# STM32Fx.net
KiCad netlist of a schematic drawn in Altium Designer
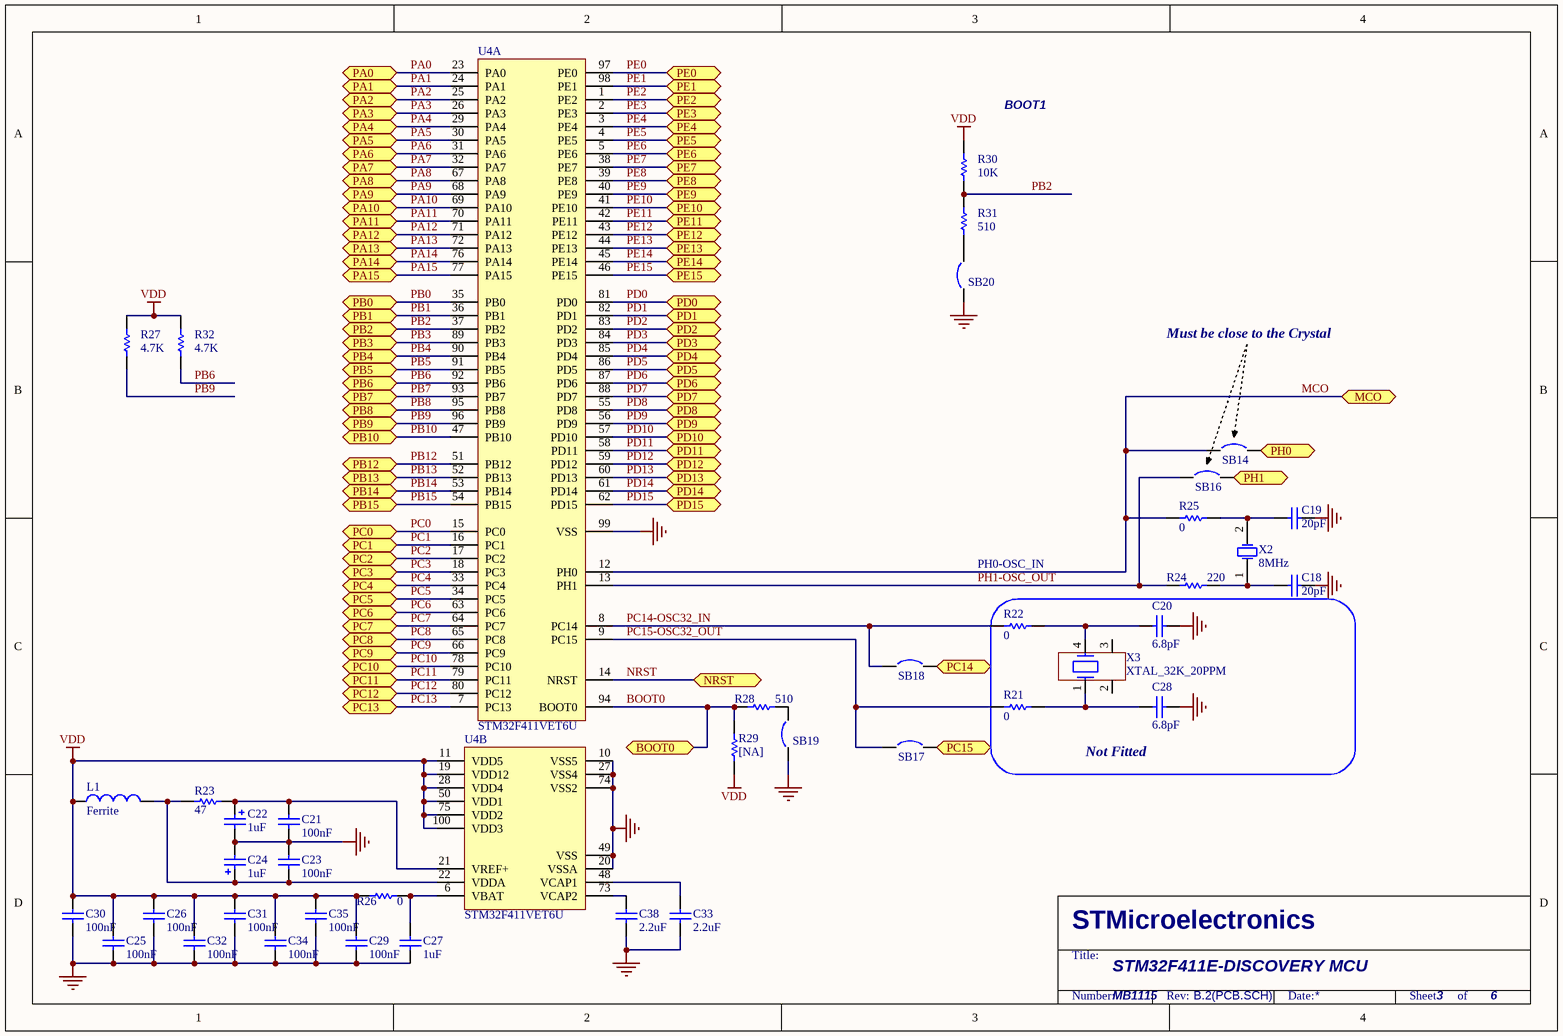
[diagram p0: STM32Fx.SchDoc]

(export (version "E")
  (design (tool "Eeschema 10.0.6"))
  (components
    (comp (ref "C18")
      (value "20pF")
      (footprint "0402C")
      (description "Capacitor,20pF,50V,NPO,5%,0402,YAGEO")
      (libsource (lib "MCD_TOOLS") (part "Cap_20pF_NPO_5%_0402"))
    )
    (comp (ref "C19")
      (value "20pF")
      (footprint "0402C")
      (description "Capacitor,20pF,50V,NPO,5%,0402,YAGEO")
      (libsource (lib "MCD_TOOLS") (part "Cap_20pF_NPO_5%_0402"))
    )
    (comp (ref "C20")
      (value "6.8pF")
      (footprint "0402C")
      (description "Capacitor,6.8pF,50V,NPO,4%,0402,AVX")
      (libsource (lib "MCD_TOOLS") (part "Cap_6.8pF_NPO_4%_0402"))
    )
    (comp (ref "C21")
      (value "100nF")
      (footprint "0402C")
      (description "Capacitor,100nF,16V,X7R,10%,0402,YAGEO")
      (libsource (lib "MCD_TOOLS") (part "Cap_100nF_X7R_10%_0402"))
    )
    (comp (ref "C22")
      (value "1uF")
      (footprint "TAN-A")
      (description "Polarized Capacitor,1uF,16V,10%,typeA,AVX")
      (libsource (lib "MCD_TOOLS") (part "Cap_1uF_POL_10%_TANA"))
    )
    (comp (ref "C23")
      (value "100nF")
      (footprint "0402C")
      (description "Capacitor,100nF,16V,X7R,10%,0402,YAGEO")
      (libsource (lib "MCD_TOOLS") (part "Cap_100nF_X7R_10%_0402"))
    )
    (comp (ref "C24")
      (value "1uF")
      (footprint "TAN-A")
      (description "Polarized Capacitor,1uF,16V,10%,typeA,AVX")
      (libsource (lib "MCD_TOOLS") (part "Cap_1uF_POL_10%_TANA"))
    )
    (comp (ref "C25")
      (value "100nF")
      (footprint "0402C")
      (description "Capacitor,100nF,16V,X7R,10%,0402,YAGEO")
      (libsource (lib "MCD_TOOLS") (part "Cap_100nF_X7R_10%_0402"))
    )
    (comp (ref "C26")
      (value "100nF")
      (footprint "0402C")
      (description "Capacitor,100nF,16V,X7R,10%,0402,YAGEO")
      (libsource (lib "MCD_TOOLS") (part "Cap_100nF_X7R_10%_0402"))
    )
    (comp (ref "C27")
      (value "1uF")
      (footprint "0603C")
      (description "Capacitor,1uF,16V,X5R,10%,0603,YAGEO")
      (libsource (lib "MCD_TOOLS") (part "Cap_1uF_X5R_10%_0603"))
    )
    (comp (ref "C28")
      (value "6.8pF")
      (footprint "0402C")
      (description "Capacitor,6.8pF,50V,NPO,4%,0402,AVX")
      (libsource (lib "MCD_TOOLS") (part "Cap_6.8pF_NPO_4%_0402"))
    )
    (comp (ref "C29")
      (value "100nF")
      (footprint "0402C")
      (description "Capacitor,100nF,16V,X7R,10%,0402,YAGEO")
      (libsource (lib "MCD_TOOLS") (part "Cap_100nF_X7R_10%_0402"))
    )
    (comp (ref "C30")
      (value "100nF")
      (footprint "0402C")
      (description "Capacitor,100nF,16V,X7R,10%,0402,YAGEO")
      (libsource (lib "MCD_TOOLS") (part "Cap_100nF_X7R_10%_0402"))
    )
    (comp (ref "C31")
      (value "100nF")
      (footprint "0402C")
      (description "Capacitor,100nF,16V,X7R,10%,0402,YAGEO")
      (libsource (lib "MCD_TOOLS") (part "Cap_100nF_X7R_10%_0402"))
    )
    (comp (ref "C32")
      (value "100nF")
      (footprint "0402C")
      (description "Capacitor,100nF,16V,X7R,10%,0402,YAGEO")
      (libsource (lib "MCD_TOOLS") (part "Cap_100nF_X7R_10%_0402"))
    )
    (comp (ref "C33")
      (value "2.2uF")
      (footprint "TAN-A")
      (description "Capacitor,2.2uF,16V, X7R,10%,0805,YAGEO")
      (libsource (lib "MCD_TOOLS") (part "Cap_2.2uF_X7R_10%_0805"))
    )
    (comp (ref "C34")
      (value "100nF")
      (footprint "0402C")
      (description "Capacitor,100nF,16V,X7R,10%,0402,YAGEO")
      (libsource (lib "MCD_TOOLS") (part "Cap_100nF_X7R_10%_0402"))
    )
    (comp (ref "C35")
      (value "100nF")
      (footprint "0402C")
      (description "Capacitor,100nF,16V,X7R,10%,0402,YAGEO")
      (libsource (lib "MCD_TOOLS") (part "Cap_100nF_X7R_10%_0402"))
    )
    (comp (ref "C38")
      (value "2.2uF")
      (footprint "TAN-A")
      (description "Capacitor,2.2uF,16V, X7R,10%,0805,YAGEO")
      (libsource (lib "MCD_TOOLS") (part "Cap_2.2uF_X7R_10%_0805"))
    )
    (comp (ref "L1")
      (value "Ferrite")
      (footprint "0603L")
      (description "Bead,600R,350mA,0603,FCM1608KF-601T03,Tai-tech")
      (libsource (lib "MCD_TOOLS") (part "BEAD_600R_350MA_0603"))
    )
    (comp (ref "R21")
      (value "0")
      (footprint "STM-SMEE:0402R")
      (description "Resistor,0,0402")
      (libsource (lib "MCD_TOOLS") (part "Res_0_0402"))
    )
    (comp (ref "R22")
      (value "0")
      (footprint "STM-SMEE:0402R")
      (description "Resistor,0,0402")
      (libsource (lib "MCD_TOOLS") (part "Res_0_0402"))
    )
    (comp (ref "R23")
      (value "47")
      (footprint "0402R")
      (description "Resistor")
      (fields (field (name "PUBLISHER") "Altium Limited"))
      (libsource (lib "Miscellaneous Devices") (part "Res1"))
    )
    (comp (ref "R24")
      (value "220")
      (footprint "0402R")
      (description "Resistor")
      (fields (field (name "PUBLISHER") "Altium Limited"))
      (libsource (lib "Miscellaneous Devices") (part "Res1"))
    )
    (comp (ref "R25")
      (value "0")
      (footprint "STM-SMEE:0402R")
      (description "Resistor,0,0402")
      (libsource (lib "MCD_TOOLS") (part "Res_0_0402"))
    )
    (comp (ref "R26")
      (value "0")
      (footprint "STM-SMEE:0402R")
      (description "Resistor,0,0402")
      (libsource (lib "MCD_TOOLS") (part "Res_0_0402"))
    )
    (comp (ref "R27")
      (value "4.7K")
      (footprint "0402R")
      (description "Resistor")
      (fields (field (name "PUBLISHER") "Altium Limited"))
      (libsource (lib "Miscellaneous Devices") (part "res1"))
    )
    (comp (ref "R28")
      (value "510")
      (footprint "0402R")
      (description "Resistor")
      (fields (field (name "PUBLISHER") "Altium Limited"))
      (libsource (lib "Miscellaneous Devices") (part "Res1"))
    )
    (comp (ref "R29")
      (value "[NA]")
      (footprint "STM-SMEE:0402R")
      (description "Resistor,[NA],0402")
      (libsource (lib "MCD_TOOLS") (part "Res_NA_0402"))
    )
    (comp (ref "R30")
      (value "10K")
      (footprint "0402R")
      (description "Resistor")
      (fields (field (name "PUBLISHER") "Altium Limited"))
      (libsource (lib "Miscellaneous Devices") (part "res1"))
    )
    (comp (ref "R31")
      (value "510")
      (footprint "0402R")
      (description "Resistor")
      (fields (field (name "PUBLISHER") "Altium Limited"))
      (libsource (lib "Miscellaneous Devices") (part "res1"))
    )
    (comp (ref "R32")
      (value "4.7K")
      (footprint "0402R")
      (description "Resistor")
      (fields (field (name "PUBLISHER") "Altium Limited"))
      (libsource (lib "Miscellaneous Devices") (part "res1"))
    )
    (comp (ref "SB14")
      (value "Circuit Breaker")
      (footprint "JP2_SMD")
      (libsource (lib "MCD_TOOLS") (part "Circuit Breaker"))
    )
    (comp (ref "SB16")
      (value "Circuit Breaker")
      (footprint "JP2_SMD")
      (libsource (lib "MCD_TOOLS") (part "Circuit Breaker"))
    )
    (comp (ref "SB17")
      (value "Circuit Breaker")
      (footprint "JP2_SMD")
      (libsource (lib "MCD_TOOLS") (part "Circuit Breaker"))
    )
    (comp (ref "SB18")
      (value "Circuit Breaker")
      (footprint "JP2_SMD")
      (libsource (lib "MCD_TOOLS") (part "Circuit Breaker"))
    )
    (comp (ref "SB19")
      (value "Circuit Breaker")
      (footprint "JP2_SMD")
      (libsource (lib "MCD_TOOLS") (part "Circuit Breaker"))
    )
    (comp (ref "SB20")
      (value "Circuit Breaker")
      (footprint "JP2_SMD")
      (libsource (lib "MCD_TOOLS") (part "Circuit Breaker"))
    )
    (comp (ref "U4")
      (value "STM32F411VET6U")
      (footprint "TQFP100")
      (description "STM32 Tiny Manta (STM32F401VCT6U)")
      (libsource (lib "MCD_TOOLS") (part "STM32F401VCT6U"))
    )
    (comp (ref "X2")
      (value "8MHz")
      (footprint "STM-SMEE:XTAL1")
      (description "Crystal Oscillator,8Mhz,20PF,20PPM,-10-70 degree,DIP,HC-49S")
      (libsource (lib "MCD_TOOLS") (part "XTAL_8MHZ_20PPM"))
    )
    (comp (ref "X3")
      (value "XTAL_32K_20PPM")
      (footprint "STM-SMEE:MC306-CRYSTAL")
      (description "crystal oscillator for clock,32.768K,6PF,20PPM,-40~85 degree,SMT,ETMB32.768W060BMPF")
      (libsource (lib "MCD_TOOLS") (part "XTAL_32K"))
    )
  )
  (nets
    (net (code "1") (name "/BOOT0") (class "Default")
      (node (ref "R28") (pin "2") (pinfunction "2_2") (pintype "passive"))
      (node (ref "R29") (pin "2") (pinfunction "2_2") (pintype "passive"))
      (node (ref "U4") (pin "94") (pinfunction "BOOT0_94") (pintype "passive"))
    )
    (net (code "2") (name "/MCO") (class "Default")
      (node (ref "R25") (pin "1") (pinfunction "1_1") (pintype "passive"))
      (node (ref "SB14") (pin "1") (pinfunction "1_1") (pintype "passive"))
      (node (ref "U4") (pin "12") (pinfunction "PH0_12") (pintype "passive"))
    )
    (net (code "3") (name "/NRST") (class "Default")
      (node (ref "U4") (pin "14") (pinfunction "NRST_14") (pintype "passive"))
    )
    (net (code "4") (name "/PA0") (class "Default")
      (node (ref "U4") (pin "23") (pinfunction "PA0_23") (pintype "passive"))
    )
    (net (code "5") (name "/PA1") (class "Default")
      (node (ref "U4") (pin "24") (pinfunction "PA1_24") (pintype "passive"))
    )
    (net (code "6") (name "/PA2") (class "Default")
      (node (ref "U4") (pin "25") (pinfunction "PA2_25") (pintype "passive"))
    )
    (net (code "7") (name "/PA3") (class "Default")
      (node (ref "U4") (pin "26") (pinfunction "PA3_26") (pintype "passive"))
    )
    (net (code "8") (name "/PA4") (class "Default")
      (node (ref "U4") (pin "29") (pinfunction "PA4_29") (pintype "passive"))
    )
    (net (code "9") (name "/PA5") (class "Default")
      (node (ref "U4") (pin "30") (pinfunction "PA5_30") (pintype "passive"))
    )
    (net (code "10") (name "/PA6") (class "Default")
      (node (ref "U4") (pin "31") (pinfunction "PA6_31") (pintype "passive"))
    )
    (net (code "11") (name "/PA7") (class "Default")
      (node (ref "U4") (pin "32") (pinfunction "PA7_32") (pintype "passive"))
    )
    (net (code "12") (name "/PA8") (class "Default")
      (node (ref "U4") (pin "67") (pinfunction "PA8_67") (pintype "passive"))
    )
    (net (code "13") (name "/PA9") (class "Default")
      (node (ref "U4") (pin "68") (pinfunction "PA9_68") (pintype "passive"))
    )
    (net (code "14") (name "/PA10") (class "Default")
      (node (ref "U4") (pin "69") (pinfunction "PA10_69") (pintype "passive"))
    )
    (net (code "15") (name "/PA11") (class "Default")
      (node (ref "U4") (pin "70") (pinfunction "PA11_70") (pintype "passive"))
    )
    (net (code "16") (name "/PA12") (class "Default")
      (node (ref "U4") (pin "71") (pinfunction "PA12_71") (pintype "passive"))
    )
    (net (code "17") (name "/PA13") (class "Default")
      (node (ref "U4") (pin "72") (pinfunction "PA13_72") (pintype "passive"))
    )
    (net (code "18") (name "/PA14") (class "Default")
      (node (ref "U4") (pin "76") (pinfunction "PA14_76") (pintype "passive"))
    )
    (net (code "19") (name "/PA15") (class "Default")
      (node (ref "U4") (pin "77") (pinfunction "PA15_77") (pintype "passive"))
    )
    (net (code "20") (name "/PB0") (class "Default")
      (node (ref "U4") (pin "35") (pinfunction "PB0_35") (pintype "passive"))
    )
    (net (code "21") (name "/PB1") (class "Default")
      (node (ref "U4") (pin "36") (pinfunction "PB1_36") (pintype "passive"))
    )
    (net (code "22") (name "/PB2") (class "Default")
      (node (ref "R30") (pin "2") (pinfunction "2_2") (pintype "passive"))
      (node (ref "R31") (pin "1") (pinfunction "1_1") (pintype "passive"))
      (node (ref "U4") (pin "37") (pinfunction "PB2_37") (pintype "passive"))
    )
    (net (code "23") (name "/PB3") (class "Default")
      (node (ref "U4") (pin "89") (pinfunction "PB3_89") (pintype "passive"))
    )
    (net (code "24") (name "/PB4") (class "Default")
      (node (ref "U4") (pin "90") (pinfunction "PB4_90") (pintype "passive"))
    )
    (net (code "25") (name "/PB5") (class "Default")
      (node (ref "U4") (pin "91") (pinfunction "PB5_91") (pintype "passive"))
    )
    (net (code "26") (name "/PB6") (class "Default")
      (node (ref "R32") (pin "2") (pinfunction "2_2") (pintype "passive"))
      (node (ref "U4") (pin "92") (pinfunction "PB6_92") (pintype "passive"))
    )
    (net (code "27") (name "/PB7") (class "Default")
      (node (ref "U4") (pin "93") (pinfunction "PB7_93") (pintype "passive"))
    )
    (net (code "28") (name "/PB8") (class "Default")
      (node (ref "U4") (pin "95") (pinfunction "PB8_95") (pintype "passive"))
    )
    (net (code "29") (name "/PB9") (class "Default")
      (node (ref "R27") (pin "2") (pinfunction "2_2") (pintype "passive"))
      (node (ref "U4") (pin "96") (pinfunction "PB9_96") (pintype "passive"))
    )
    (net (code "30") (name "/PB10") (class "Default")
      (node (ref "U4") (pin "47") (pinfunction "PB10_47") (pintype "passive"))
    )
    (net (code "31") (name "/PB12") (class "Default")
      (node (ref "U4") (pin "51") (pinfunction "PB12_51") (pintype "passive"))
    )
    (net (code "32") (name "/PB13") (class "Default")
      (node (ref "U4") (pin "52") (pinfunction "PB13_52") (pintype "passive"))
    )
    (net (code "33") (name "/PB14") (class "Default")
      (node (ref "U4") (pin "53") (pinfunction "PB14_53") (pintype "passive"))
    )
    (net (code "34") (name "/PB15") (class "Default")
      (node (ref "U4") (pin "54") (pinfunction "PB15_54") (pintype "passive"))
    )
    (net (code "35") (name "/PC0") (class "Default")
      (node (ref "U4") (pin "15") (pinfunction "PC0_15") (pintype "passive"))
    )
    (net (code "36") (name "/PC1") (class "Default")
      (node (ref "U4") (pin "16") (pinfunction "PC1_16") (pintype "passive"))
    )
    (net (code "37") (name "/PC2") (class "Default")
      (node (ref "U4") (pin "17") (pinfunction "PC2_17") (pintype "passive"))
    )
    (net (code "38") (name "/PC3") (class "Default")
      (node (ref "U4") (pin "18") (pinfunction "PC3_18") (pintype "passive"))
    )
    (net (code "39") (name "/PC4") (class "Default")
      (node (ref "U4") (pin "33") (pinfunction "PC4_33") (pintype "passive"))
    )
    (net (code "40") (name "/PC5") (class "Default")
      (node (ref "U4") (pin "34") (pinfunction "PC5_34") (pintype "passive"))
    )
    (net (code "41") (name "/PC6") (class "Default")
      (node (ref "U4") (pin "63") (pinfunction "PC6_63") (pintype "passive"))
    )
    (net (code "42") (name "/PC7") (class "Default")
      (node (ref "U4") (pin "64") (pinfunction "PC7_64") (pintype "passive"))
    )
    (net (code "43") (name "/PC8") (class "Default")
      (node (ref "U4") (pin "65") (pinfunction "PC8_65") (pintype "passive"))
    )
    (net (code "44") (name "/PC9") (class "Default")
      (node (ref "U4") (pin "66") (pinfunction "PC9_66") (pintype "passive"))
    )
    (net (code "45") (name "/PC10") (class "Default")
      (node (ref "U4") (pin "78") (pinfunction "PC10_78") (pintype "passive"))
    )
    (net (code "46") (name "/PC11") (class "Default")
      (node (ref "U4") (pin "79") (pinfunction "PC11_79") (pintype "passive"))
    )
    (net (code "47") (name "/PC12") (class "Default")
      (node (ref "U4") (pin "80") (pinfunction "PC12_80") (pintype "passive"))
    )
    (net (code "48") (name "/PC13") (class "Default")
      (node (ref "U4") (pin "7") (pinfunction "PC13_7") (pintype "passive"))
    )
    (net (code "49") (name "/PC14") (class "Default")
      (node (ref "SB18") (pin "2") (pinfunction "2_2") (pintype "passive"))
    )
    (net (code "50") (name "/PC14-OSC32_IN") (class "Default")
      (node (ref "R22") (pin "1") (pinfunction "1_1") (pintype "passive"))
      (node (ref "SB18") (pin "1") (pinfunction "1_1") (pintype "passive"))
      (node (ref "U4") (pin "8") (pinfunction "PC14_8") (pintype "passive"))
    )
    (net (code "51") (name "/PC15") (class "Default")
      (node (ref "SB17") (pin "2") (pinfunction "2_2") (pintype "passive"))
    )
    (net (code "52") (name "/PC15-OSC32_OUT") (class "Default")
      (node (ref "R21") (pin "1") (pinfunction "1_1") (pintype "passive"))
      (node (ref "SB17") (pin "1") (pinfunction "1_1") (pintype "passive"))
      (node (ref "U4") (pin "9") (pinfunction "PC15_9") (pintype "passive"))
    )
    (net (code "53") (name "/PD0") (class "Default")
      (node (ref "U4") (pin "81") (pinfunction "PD0_81") (pintype "passive"))
    )
    (net (code "54") (name "/PD1") (class "Default")
      (node (ref "U4") (pin "82") (pinfunction "PD1_82") (pintype "passive"))
    )
    (net (code "55") (name "/PD2") (class "Default")
      (node (ref "U4") (pin "83") (pinfunction "PD2_83") (pintype "passive"))
    )
    (net (code "56") (name "/PD3") (class "Default")
      (node (ref "U4") (pin "84") (pinfunction "PD3_84") (pintype "passive"))
    )
    (net (code "57") (name "/PD4") (class "Default")
      (node (ref "U4") (pin "85") (pinfunction "PD4_85") (pintype "passive"))
    )
    (net (code "58") (name "/PD5") (class "Default")
      (node (ref "U4") (pin "86") (pinfunction "PD5_86") (pintype "passive"))
    )
    (net (code "59") (name "/PD6") (class "Default")
      (node (ref "U4") (pin "87") (pinfunction "PD6_87") (pintype "passive"))
    )
    (net (code "60") (name "/PD7") (class "Default")
      (node (ref "U4") (pin "88") (pinfunction "PD7_88") (pintype "passive"))
    )
    (net (code "61") (name "/PD8") (class "Default")
      (node (ref "U4") (pin "55") (pinfunction "PD8_55") (pintype "passive"))
    )
    (net (code "62") (name "/PD9") (class "Default")
      (node (ref "U4") (pin "56") (pinfunction "PD9_56") (pintype "passive"))
    )
    (net (code "63") (name "/PD10") (class "Default")
      (node (ref "U4") (pin "57") (pinfunction "PD10_57") (pintype "passive"))
    )
    (net (code "64") (name "/PD11") (class "Default")
      (node (ref "U4") (pin "58") (pinfunction "PD11_58") (pintype "passive"))
    )
    (net (code "65") (name "/PD12") (class "Default")
      (node (ref "U4") (pin "59") (pinfunction "PD12_59") (pintype "passive"))
    )
    (net (code "66") (name "/PD13") (class "Default")
      (node (ref "U4") (pin "60") (pinfunction "PD13_60") (pintype "passive"))
    )
    (net (code "67") (name "/PD14") (class "Default")
      (node (ref "U4") (pin "61") (pinfunction "PD14_61") (pintype "passive"))
    )
    (net (code "68") (name "/PD15") (class "Default")
      (node (ref "U4") (pin "62") (pinfunction "PD15_62") (pintype "passive"))
    )
    (net (code "69") (name "/PE0") (class "Default")
      (node (ref "U4") (pin "97") (pinfunction "PE0_97") (pintype "passive"))
    )
    (net (code "70") (name "/PE1") (class "Default")
      (node (ref "U4") (pin "98") (pinfunction "PE1_98") (pintype "passive"))
    )
    (net (code "71") (name "/PE2") (class "Default")
      (node (ref "U4") (pin "1") (pinfunction "PE2_1") (pintype "passive"))
    )
    (net (code "72") (name "/PE3") (class "Default")
      (node (ref "U4") (pin "2") (pinfunction "PE3_2") (pintype "passive"))
    )
    (net (code "73") (name "/PE4") (class "Default")
      (node (ref "U4") (pin "3") (pinfunction "PE4_3") (pintype "passive"))
    )
    (net (code "74") (name "/PE5") (class "Default")
      (node (ref "U4") (pin "4") (pinfunction "PE5_4") (pintype "passive"))
    )
    (net (code "75") (name "/PE6") (class "Default")
      (node (ref "U4") (pin "5") (pinfunction "PE6_5") (pintype "passive"))
    )
    (net (code "76") (name "/PE7") (class "Default")
      (node (ref "U4") (pin "38") (pinfunction "PE7_38") (pintype "passive"))
    )
    (net (code "77") (name "/PE8") (class "Default")
      (node (ref "U4") (pin "39") (pinfunction "PE8_39") (pintype "passive"))
    )
    (net (code "78") (name "/PE9") (class "Default")
      (node (ref "U4") (pin "40") (pinfunction "PE9_40") (pintype "passive"))
    )
    (net (code "79") (name "/PE10") (class "Default")
      (node (ref "U4") (pin "41") (pinfunction "PE10_41") (pintype "passive"))
    )
    (net (code "80") (name "/PE11") (class "Default")
      (node (ref "U4") (pin "42") (pinfunction "PE11_42") (pintype "passive"))
    )
    (net (code "81") (name "/PE12") (class "Default")
      (node (ref "U4") (pin "43") (pinfunction "PE12_43") (pintype "passive"))
    )
    (net (code "82") (name "/PE13") (class "Default")
      (node (ref "U4") (pin "44") (pinfunction "PE13_44") (pintype "passive"))
    )
    (net (code "83") (name "/PE14") (class "Default")
      (node (ref "U4") (pin "45") (pinfunction "PE14_45") (pintype "passive"))
    )
    (net (code "84") (name "/PE15") (class "Default")
      (node (ref "U4") (pin "46") (pinfunction "PE15_46") (pintype "passive"))
    )
    (net (code "85") (name "/PH0") (class "Default")
      (node (ref "SB14") (pin "2") (pinfunction "2_2") (pintype "passive"))
    )
    (net (code "86") (name "/PH1") (class "Default")
      (node (ref "SB16") (pin "2") (pinfunction "2_2") (pintype "passive"))
    )
    (net (code "87") (name "/PH1-OSC_OUT") (class "Default")
      (node (ref "R24") (pin "2") (pinfunction "2_2") (pintype "passive"))
      (node (ref "SB16") (pin "1") (pinfunction "1_1") (pintype "passive"))
      (node (ref "U4") (pin "13") (pinfunction "PH1_13") (pintype "passive"))
    )
    (net (code "88") (name "GND") (class "Default")
      (node (ref "C18") (pin "1") (pinfunction "1_1") (pintype "passive"))
      (node (ref "C19") (pin "1") (pinfunction "1_1") (pintype "passive"))
      (node (ref "C20") (pin "2") (pinfunction "2_2") (pintype "passive"))
      (node (ref "C21") (pin "1") (pinfunction "1_1") (pintype "passive"))
      (node (ref "C22") (pin "2") (pinfunction "2_2") (pintype "passive"))
      (node (ref "C23") (pin "1") (pinfunction "1_1") (pintype "passive"))
      (node (ref "C24") (pin "2") (pinfunction "2_2") (pintype "passive"))
      (node (ref "C25") (pin "1") (pinfunction "1_1") (pintype "passive"))
      (node (ref "C26") (pin "2") (pinfunction "2_2") (pintype "passive"))
      (node (ref "C27") (pin "2") (pinfunction "2_2") (pintype "passive"))
      (node (ref "C28") (pin "2") (pinfunction "2_2") (pintype "passive"))
      (node (ref "C29") (pin "1") (pinfunction "1_1") (pintype "passive"))
      (node (ref "C30") (pin "1") (pinfunction "1_1") (pintype "passive"))
      (node (ref "C31") (pin "1") (pinfunction "1_1") (pintype "passive"))
      (node (ref "C32") (pin "1") (pinfunction "1_1") (pintype "passive"))
      (node (ref "C33") (pin "2") (pinfunction "2_2") (pintype "passive"))
      (node (ref "C34") (pin "1") (pinfunction "1_1") (pintype "passive"))
      (node (ref "C35") (pin "2") (pinfunction "2_2") (pintype "passive"))
      (node (ref "C38") (pin "2") (pinfunction "2_2") (pintype "passive"))
      (node (ref "SB19") (pin "1") (pinfunction "1_1") (pintype "passive"))
      (node (ref "SB20") (pin "1") (pinfunction "1_1") (pintype "passive"))
      (node (ref "U4") (pin "10") (pinfunction "VSS5_10") (pintype "passive"))
      (node (ref "U4") (pin "20") (pinfunction "VSSA_20") (pintype "passive"))
      (node (ref "U4") (pin "27") (pinfunction "VSS4_27") (pintype "passive"))
      (node (ref "U4") (pin "49") (pinfunction "VSS_49") (pintype "passive"))
      (node (ref "U4") (pin "74") (pinfunction "VSS2_74") (pintype "passive"))
      (node (ref "U4") (pin "99") (pinfunction "VSS_99") (pintype "passive"))
    )
    (net (code "89") (name "Net-(C20-Pad1)") (class "Default")
      (node (ref "C20") (pin "1") (pinfunction "1_1") (pintype "passive"))
      (node (ref "R22") (pin "2") (pinfunction "2_2") (pintype "passive"))
      (node (ref "X3") (pin "4") (pinfunction "4_4") (pintype "passive"))
    )
    (net (code "90") (name "Net-(C28-Pad1)") (class "Default")
      (node (ref "C28") (pin "1") (pinfunction "1_1") (pintype "passive"))
      (node (ref "R21") (pin "2") (pinfunction "2_2") (pintype "passive"))
      (node (ref "X3") (pin "1") (pinfunction "1_1") (pintype "passive"))
    )
    (net (code "91") (name "Net-(R28-Pad1)") (class "Default")
      (node (ref "R28") (pin "1") (pinfunction "1_1") (pintype "passive"))
      (node (ref "SB19") (pin "2") (pinfunction "2_2") (pintype "passive"))
    )
    (net (code "92") (name "Net-(R31-Pad2)") (class "Default")
      (node (ref "R31") (pin "2") (pinfunction "2_2") (pintype "passive"))
      (node (ref "SB20") (pin "2") (pinfunction "2_2") (pintype "passive"))
    )
    (net (code "93") (name "Net-(U4B-VBAT)") (class "Default")
      (node (ref "C27") (pin "1") (pinfunction "1_1") (pintype "passive"))
      (node (ref "R26") (pin "2") (pinfunction "2_2") (pintype "passive"))
      (node (ref "U4") (pin "6") (pinfunction "VBAT_6") (pintype "passive"))
    )
    (net (code "94") (name "Net-(U4B-VCAP1)") (class "Default")
      (node (ref "C33") (pin "1") (pinfunction "1_1") (pintype "passive"))
      (node (ref "U4") (pin "48") (pinfunction "VCAP1_48") (pintype "passive"))
    )
    (net (code "95") (name "Net-(U4B-VCAP2)") (class "Default")
      (node (ref "C38") (pin "1") (pinfunction "1_1") (pintype "passive"))
      (node (ref "U4") (pin "73") (pinfunction "VCAP2_73") (pintype "passive"))
    )
    (net (code "96") (name "Net-(U4B-VDDA)") (class "Default")
      (node (ref "C23") (pin "2") (pinfunction "2_2") (pintype "passive"))
      (node (ref "C24") (pin "1") (pinfunction "1_1") (pintype "passive"))
      (node (ref "L1") (pin "2") (pinfunction "2_2") (pintype "passive"))
      (node (ref "R23") (pin "2") (pinfunction "2_2") (pintype "passive"))
      (node (ref "U4") (pin "22") (pinfunction "VDDA_22") (pintype "passive"))
    )
    (net (code "97") (name "Net-(U4B-VREF+)") (class "Default")
      (node (ref "C21") (pin "2") (pinfunction "2_2") (pintype "passive"))
      (node (ref "C22") (pin "1") (pinfunction "1_1") (pintype "passive"))
      (node (ref "R23") (pin "1") (pinfunction "1_1") (pintype "passive"))
      (node (ref "U4") (pin "21") (pinfunction "VREF+_21") (pintype "passive"))
    )
    (net (code "98") (name "Net-(X2-OSC1)") (class "Default")
      (node (ref "C18") (pin "2") (pinfunction "2_2") (pintype "passive"))
      (node (ref "R24") (pin "1") (pinfunction "1_1") (pintype "passive"))
      (node (ref "X2") (pin "1") (pinfunction "OSC1_1") (pintype "passive"))
    )
    (net (code "99") (name "Net-(X2-OSC2)") (class "Default")
      (node (ref "C19") (pin "2") (pinfunction "2_2") (pintype "passive"))
      (node (ref "R25") (pin "2") (pinfunction "2_2") (pintype "passive"))
      (node (ref "X2") (pin "2") (pinfunction "OSC2_2") (pintype "passive"))
    )
    (net (code "100") (name "VDD") (class "Default")
      (node (ref "C25") (pin "2") (pinfunction "2_2") (pintype "passive"))
      (node (ref "C26") (pin "1") (pinfunction "1_1") (pintype "passive"))
      (node (ref "C29") (pin "2") (pinfunction "2_2") (pintype "passive"))
      (node (ref "C30") (pin "2") (pinfunction "2_2") (pintype "passive"))
      (node (ref "C31") (pin "2") (pinfunction "2_2") (pintype "passive"))
      (node (ref "C32") (pin "2") (pinfunction "2_2") (pintype "passive"))
      (node (ref "C34") (pin "2") (pinfunction "2_2") (pintype "passive"))
      (node (ref "C35") (pin "1") (pinfunction "1_1") (pintype "passive"))
      (node (ref "L1") (pin "1") (pinfunction "1_1") (pintype "passive"))
      (node (ref "R26") (pin "1") (pinfunction "1_1") (pintype "passive"))
      (node (ref "R27") (pin "1") (pinfunction "1_1") (pintype "passive"))
      (node (ref "R29") (pin "1") (pinfunction "1_1") (pintype "passive"))
      (node (ref "R30") (pin "1") (pinfunction "1_1") (pintype "passive"))
      (node (ref "R32") (pin "1") (pinfunction "1_1") (pintype "passive"))
      (node (ref "U4") (pin "100") (pinfunction "VDD3_100") (pintype "passive"))
      (node (ref "U4") (pin "11") (pinfunction "VDD5_11") (pintype "passive"))
      (node (ref "U4") (pin "19") (pinfunction "VDD12_19") (pintype "passive"))
      (node (ref "U4") (pin "28") (pinfunction "VDD4_28") (pintype "passive"))
      (node (ref "U4") (pin "50") (pinfunction "VDD1_50") (pintype "passive"))
      (node (ref "U4") (pin "75") (pinfunction "VDD2_75") (pintype "passive"))
    )
    (net (code "101") (name "unconnected-(X3-Pad2)") (class "Default")
      (node (ref "X3") (pin "2") (pinfunction "2_2") (pintype "passive"))
    )
    (net (code "102") (name "unconnected-(X3-Pad3)") (class "Default")
      (node (ref "X3") (pin "3") (pinfunction "3_3") (pintype "passive"))
    )
  )
)
